# Primary_system.net
KiCad netlist of a schematic drawn in EAGLE
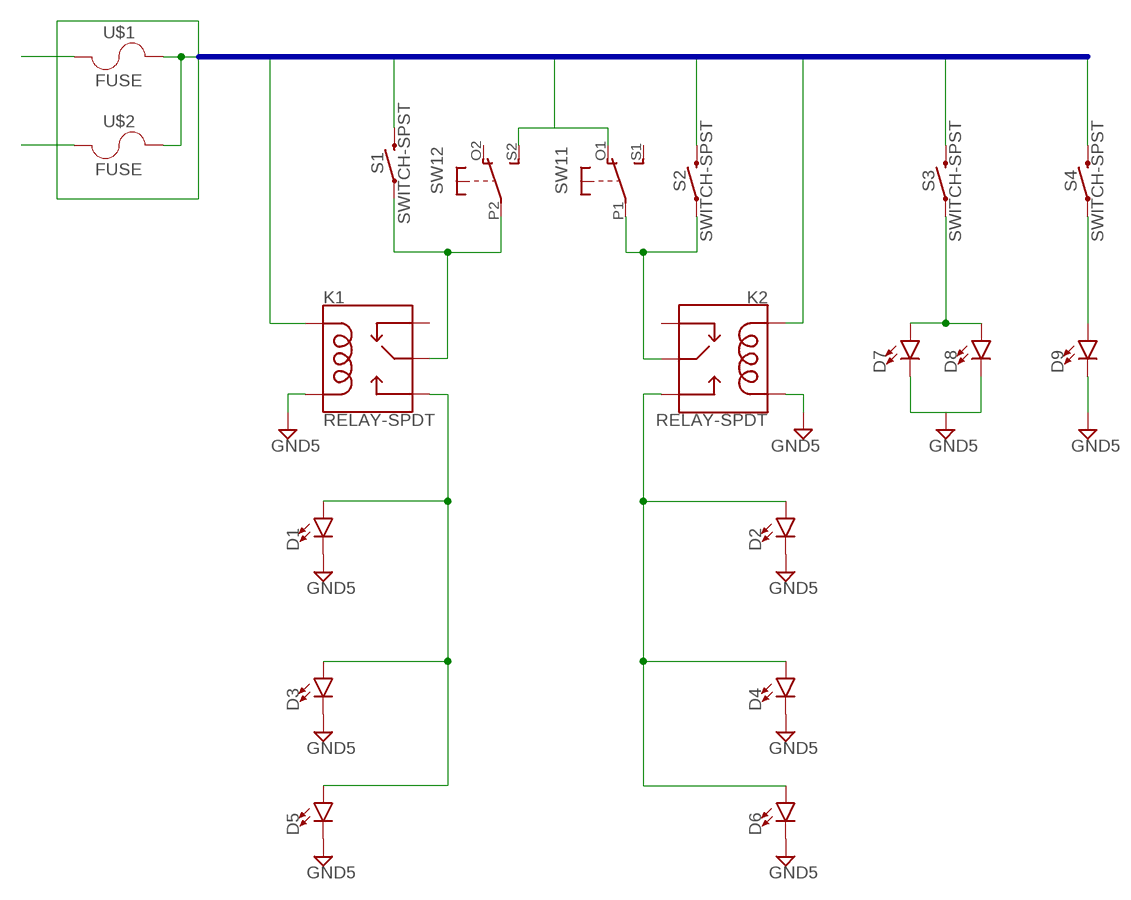
[diagram p0: schematic, sheet 1]

(export (version "E")
  (design (tool "Eeschema 10.0.6"))
  (components
    (comp (ref "D1")
      (value "LED5MM")
      (footprint "eagle-import:LED_5MM")
      (libsource (lib "eagle-import") (part "LED5MM"))
    )
    (comp (ref "D2")
      (value "LED5MM")
      (footprint "eagle-import:LED_5MM")
      (libsource (lib "eagle-import") (part "LED5MM"))
    )
    (comp (ref "D3")
      (value "LED5MM")
      (footprint "eagle-import:LED_5MM")
      (libsource (lib "eagle-import") (part "LED5MM"))
    )
    (comp (ref "D4")
      (value "LED5MM")
      (footprint "eagle-import:LED_5MM")
      (libsource (lib "eagle-import") (part "LED5MM"))
    )
    (comp (ref "D5")
      (value "LED5MM")
      (footprint "eagle-import:LED_5MM")
      (libsource (lib "eagle-import") (part "LED5MM"))
    )
    (comp (ref "D6")
      (value "LED5MM")
      (footprint "eagle-import:LED_5MM")
      (libsource (lib "eagle-import") (part "LED5MM"))
    )
    (comp (ref "D7")
      (value "LED5MM")
      (footprint "eagle-import:LED_5MM")
      (libsource (lib "eagle-import") (part "LED5MM"))
    )
    (comp (ref "D8")
      (value "LED5MM")
      (footprint "eagle-import:LED_5MM")
      (libsource (lib "eagle-import") (part "LED5MM"))
    )
    (comp (ref "D9")
      (value "LED5MM")
      (footprint "eagle-import:LED_5MM")
      (libsource (lib "eagle-import") (part "LED5MM"))
    )
    (comp (ref "K1")
      (value "RELAY-SPDT")
      (footprint "eagle-import:RELAY_G5LE")
      (libsource (lib "eagle-import") (part "RELAY-SPDT"))
    )
    (comp (ref "K2")
      (value "RELAY-SPDT")
      (footprint "eagle-import:RELAY_G5LE")
      (libsource (lib "eagle-import") (part "RELAY-SPDT"))
    )
    (comp (ref "S1")
      (value "SWITCH-SPST")
      (footprint "eagle-import:TACTILE_SWITCH_PTH_6.0MM")
      (libsource (lib "eagle-import") (part "MOMENTARY-SWITCH-SPST-PTH-6.0MM"))
    )
    (comp (ref "S2")
      (value "SWITCH-SPST")
      (footprint "eagle-import:TACTILE_SWITCH_PTH_6.0MM")
      (libsource (lib "eagle-import") (part "MOMENTARY-SWITCH-SPST-PTH-6.0MM"))
    )
    (comp (ref "S3")
      (value "SWITCH-SPST")
      (footprint "eagle-import:TACTILE_SWITCH_PTH_6.0MM")
      (libsource (lib "eagle-import") (part "MOMENTARY-SWITCH-SPST-PTH-6.0MM"))
    )
    (comp (ref "S4")
      (value "SWITCH-SPST")
      (footprint "eagle-import:TACTILE_SWITCH_PTH_6.0MM")
      (libsource (lib "eagle-import") (part "MOMENTARY-SWITCH-SPST-PTH-6.0MM"))
    )
    (comp (ref "SW1")
      (value "DPDT-EG1390")
      (footprint "eagle-import:EG1390")
      (libsource (lib "eagle-import") (part "DPDT-EG1390"))
    )
    (comp (ref "U$1")
      (value "FUSE")
      (footprint "eagle-import:0805")
      (libsource (lib "eagle-import") (part "FUSE"))
    )
    (comp (ref "U$2")
      (value "FUSE")
      (footprint "eagle-import:0805")
      (libsource (lib "eagle-import") (part "FUSE"))
    )
  )
  (nets
    (net (code "1") (name "/N$2") (class "Default")
      (node (ref "K1") (pin "2") (pinfunction "COIL1_2") (pintype "bidirectional"))
      (node (ref "K2") (pin "2") (pinfunction "COIL1_2") (pintype "bidirectional"))
      (node (ref "S1") (pin "3") (pinfunction "2_3") (pintype "passive"))
      (node (ref "S2") (pin "3") (pinfunction "2_3") (pintype "passive"))
      (node (ref "S3") (pin "3") (pinfunction "2_3") (pintype "passive"))
      (node (ref "S4") (pin "3") (pinfunction "2_3") (pintype "passive"))
    )
    (net (code "2") (name "GND5") (class "Default")
      (node (ref "D1") (pin "K") (pinfunction "C_K") (pintype "passive"))
      (node (ref "D2") (pin "K") (pinfunction "C_K") (pintype "passive"))
      (node (ref "D3") (pin "K") (pinfunction "C_K") (pintype "passive"))
      (node (ref "D4") (pin "K") (pinfunction "C_K") (pintype "passive"))
      (node (ref "D5") (pin "K") (pinfunction "C_K") (pintype "passive"))
      (node (ref "D6") (pin "K") (pinfunction "C_K") (pintype "passive"))
      (node (ref "D7") (pin "K") (pinfunction "C_K") (pintype "passive"))
      (node (ref "D8") (pin "K") (pinfunction "C_K") (pintype "passive"))
      (node (ref "D9") (pin "K") (pinfunction "C_K") (pintype "passive"))
      (node (ref "K1") (pin "5") (pinfunction "COIL2_5") (pintype "bidirectional"))
      (node (ref "K2") (pin "5") (pinfunction "COIL2_5") (pintype "bidirectional"))
    )
    (net (code "3") (name "Net-(D7-PadA)") (class "Default")
      (node (ref "D7") (pin "A") (pinfunction "A_A") (pintype "passive"))
      (node (ref "D8") (pin "A") (pinfunction "A_A") (pintype "passive"))
      (node (ref "S3") (pin "1") (pinfunction "1_1") (pintype "passive"))
    )
    (net (code "4") (name "Net-(D9-PadA)") (class "Default")
      (node (ref "D9") (pin "A") (pinfunction "A_A") (pintype "passive"))
      (node (ref "S4") (pin "1") (pinfunction "1_1") (pintype "passive"))
    )
    (net (code "5") (name "Net-(K1-MAIN)") (class "Default")
      (node (ref "K1") (pin "1") (pinfunction "MAIN_1") (pintype "bidirectional"))
      (node (ref "S1") (pin "1") (pinfunction "1_1") (pintype "passive"))
      (node (ref "SW1") (pin "P2") (pinfunction "P_P2") (pintype "passive"))
    )
    (net (code "6") (name "Net-(K1-NO)") (class "Default")
      (node (ref "D1") (pin "A") (pinfunction "A_A") (pintype "passive"))
      (node (ref "D3") (pin "A") (pinfunction "A_A") (pintype "passive"))
      (node (ref "D5") (pin "A") (pinfunction "A_A") (pintype "passive"))
      (node (ref "K1") (pin "3") (pinfunction "NO_3") (pintype "bidirectional"))
    )
    (net (code "7") (name "Net-(K2-MAIN)") (class "Default")
      (node (ref "K2") (pin "1") (pinfunction "MAIN_1") (pintype "bidirectional"))
      (node (ref "S2") (pin "1") (pinfunction "1_1") (pintype "passive"))
      (node (ref "SW1") (pin "P1") (pinfunction "P_P1") (pintype "passive"))
    )
    (net (code "8") (name "Net-(K2-NO)") (class "Default")
      (node (ref "D2") (pin "A") (pinfunction "A_A") (pintype "passive"))
      (node (ref "D4") (pin "A") (pinfunction "A_A") (pintype "passive"))
      (node (ref "D6") (pin "A") (pinfunction "A_A") (pintype "passive"))
      (node (ref "K2") (pin "3") (pinfunction "NO_3") (pintype "bidirectional"))
    )
    (net (code "9") (name "Net-(SW1A-O)") (class "Default")
      (node (ref "SW1") (pin "O1") (pinfunction "O_O1") (pintype "passive"))
      (node (ref "SW1") (pin "S2") (pinfunction "S_S2") (pintype "passive"))
    )
    (net (code "10") (name "Net-(U$1-Pad2)") (class "Default")
      (node (ref "U$1") (pin "2") (pinfunction "2_2") (pintype "bidirectional"))
      (node (ref "U$2") (pin "2") (pinfunction "2_2") (pintype "bidirectional"))
    )
    (net (code "11") (name "unconnected-(K1-NC-Pad4)") (class "Default")
      (node (ref "K1") (pin "4") (pinfunction "NC_4") (pintype "bidirectional"))
    )
    (net (code "12") (name "unconnected-(K2-NC-Pad4)") (class "Default")
      (node (ref "K2") (pin "4") (pinfunction "NC_4") (pintype "bidirectional"))
    )
    (net (code "13") (name "unconnected-(SW1A-S-PadS1)") (class "Default")
      (node (ref "SW1") (pin "S1") (pinfunction "S_S1") (pintype "passive"))
    )
    (net (code "14") (name "unconnected-(SW1B-O-PadO2)") (class "Default")
      (node (ref "SW1") (pin "O2") (pinfunction "O_O2") (pintype "passive"))
    )
    (net (code "15") (name "unconnected-(U$1-Pad1)") (class "Default")
      (node (ref "U$1") (pin "1") (pinfunction "1_1") (pintype "bidirectional"))
    )
    (net (code "16") (name "unconnected-(U$2-Pad1)") (class "Default")
      (node (ref "U$2") (pin "1") (pinfunction "1_1") (pintype "bidirectional"))
    )
  )
)
